# Teensy_ETH.net
KiCad netlist of a schematic drawn in EAGLE
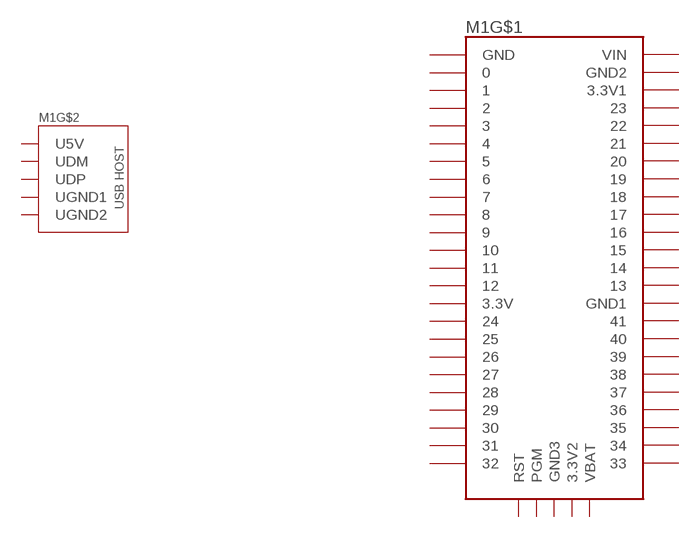
[diagram p0: schematic, sheet 1]
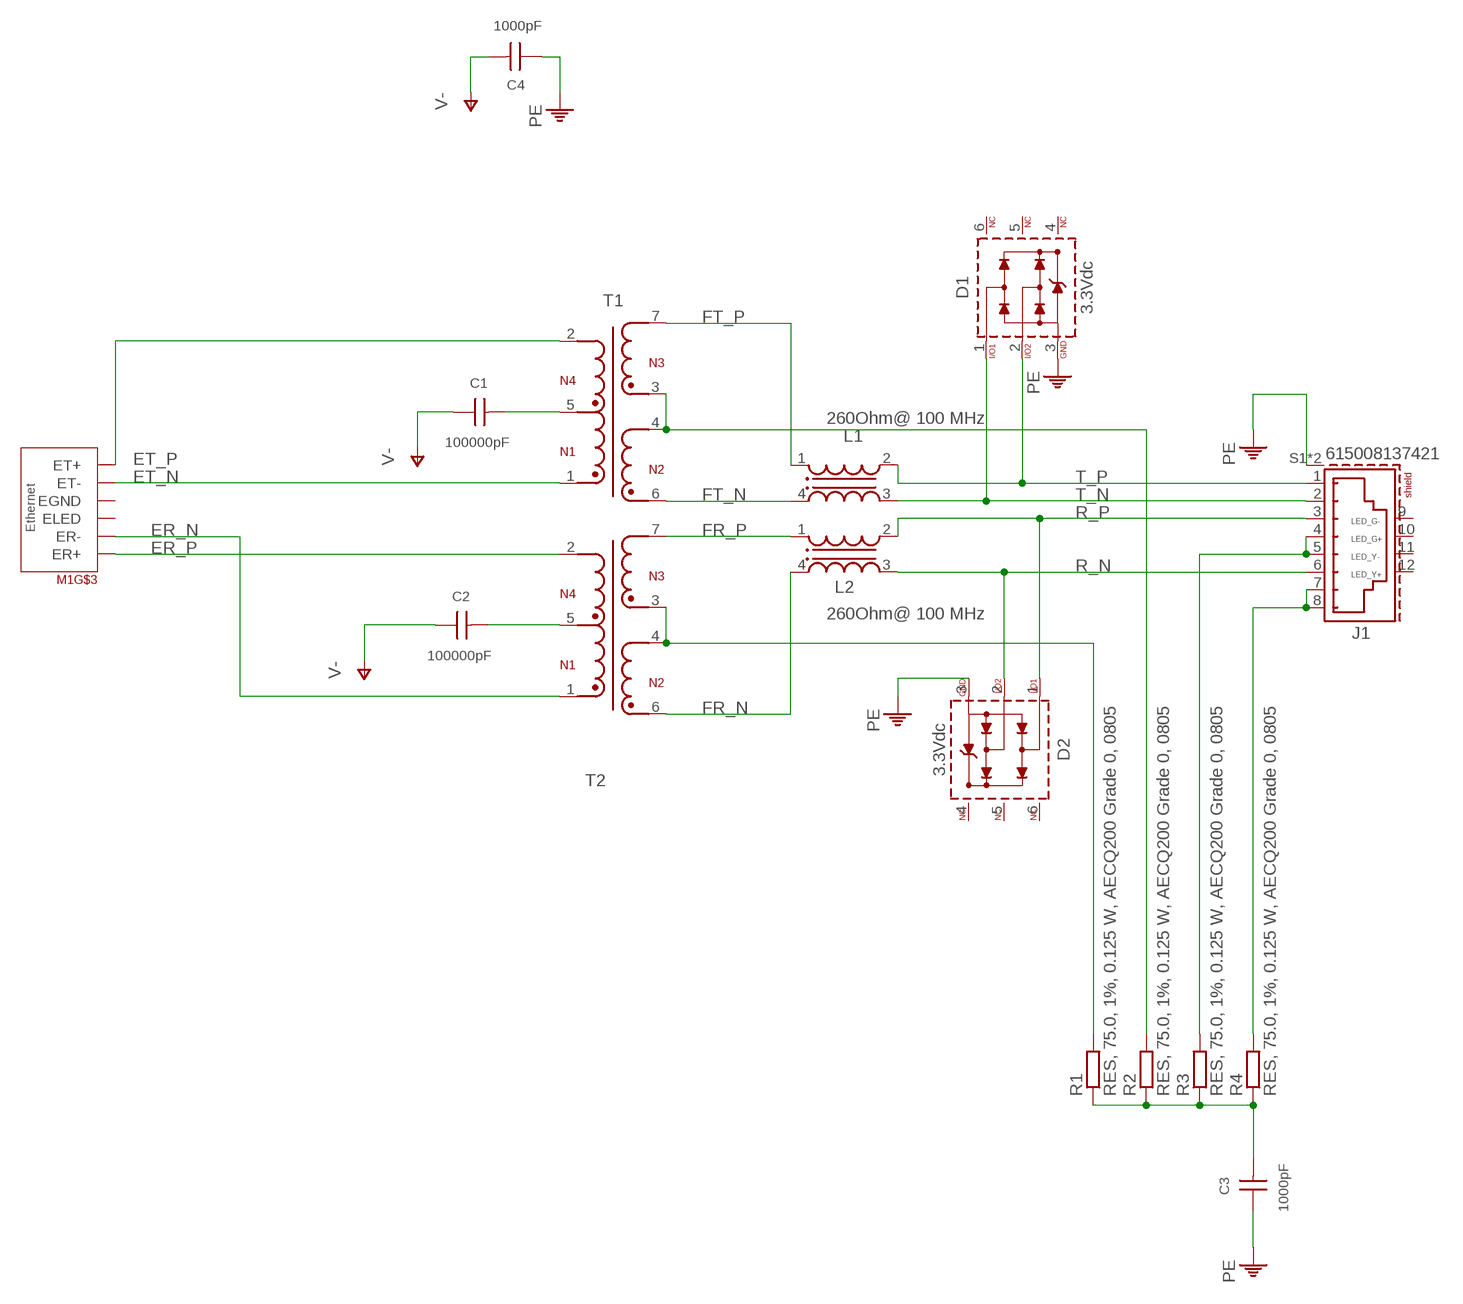
[diagram p1: schematic, sheet 2]

(export (version "E")
  (design (tool "Eeschema 10.0.6"))
  (components
    (comp (ref "C1")
      (value "100000pF")
      (footprint "eagle-import:WCAP-CSST_0603_R")
      (libsource (lib "eagle-import") (part "WCAP-CSST_0603_R_885382206004"))
    )
    (comp (ref "C2")
      (value "100000pF")
      (footprint "eagle-import:WCAP-CSST_0603_R")
      (libsource (lib "eagle-import") (part "WCAP-CSST_0603_R_885382206004"))
    )
    (comp (ref "C3")
      (value "1000pF")
      (footprint "eagle-import:WCAP-CSMH_1206_H1.6_R")
      (libsource (lib "eagle-import") (part "WCAP-CSMH_1206_H1.6_885342208024"))
    )
    (comp (ref "C4")
      (value "1000pF")
      (footprint "eagle-import:WCAP-CSMH_1206_H1.6_R")
      (libsource (lib "eagle-import") (part "WCAP-CSMH_1206_H1.6_885342208024"))
    )
    (comp (ref "D1")
      (value "3.3Vdc")
      (footprint "eagle-import:WE-TVS_DFN1210-6L")
      (libsource (lib "eagle-import") (part "WE-TVS-SS_DFN1210-6L_824012823"))
    )
    (comp (ref "D2")
      (value "3.3Vdc")
      (footprint "eagle-import:WE-TVS_DFN1210-6L")
      (libsource (lib "eagle-import") (part "WE-TVS-SS_DFN1210-6L_824012823"))
    )
    (comp (ref "J1")
      (value "615008137421")
      (footprint "eagle-import:615008137421")
      (libsource (lib "eagle-import") (part "615008137421"))
    )
    (comp (ref "L1")
      (value "260Ohm@ 100 MHz")
      (footprint "eagle-import:WE-CNSW_0805")
      (libsource (lib "eagle-import") (part "WE-CNSW_0805_744231261"))
    )
    (comp (ref "L2")
      (value "260Ohm@ 100 MHz")
      (footprint "eagle-import:WE-CNSW_0805")
      (libsource (lib "eagle-import") (part "WE-CNSW_0805_744231261"))
    )
    (comp (ref "M1")
      (value "TEENSY4.1")
      (footprint "eagle-import:TEENSY4.1")
      (libsource (lib "eagle-import") (part "TEENSY4.1"))
    )
    (comp (ref "R1")
      (value "RES, 75.0, 1%, 0.125 W, AECQ200 Grade 0, 0805")
      (footprint "eagle-import:R0805")
      (libsource (lib "eagle-import") (part "R-EU_R0805"))
    )
    (comp (ref "R2")
      (value "RES, 75.0, 1%, 0.125 W, AECQ200 Grade 0, 0805")
      (footprint "eagle-import:R0805")
      (libsource (lib "eagle-import") (part "R-EU_R0805"))
    )
    (comp (ref "R3")
      (value "RES, 75.0, 1%, 0.125 W, AECQ200 Grade 0, 0805")
      (footprint "eagle-import:R0805")
      (libsource (lib "eagle-import") (part "R-EU_R0805"))
    )
    (comp (ref "R4")
      (value "RES, 75.0, 1%, 0.125 W, AECQ200 Grade 0, 0805")
      (footprint "eagle-import:R0805")
      (libsource (lib "eagle-import") (part "R-EU_R0805"))
    )
    (comp (ref "T1")
      (value "WE-STST_4532_74930000")
      (footprint "eagle-import:WE-STST_74930000")
      (libsource (lib "eagle-import") (part "WE-STST_4532_74930000"))
    )
    (comp (ref "T2")
      (value "WE-STST_4532_74930000")
      (footprint "eagle-import:WE-STST_74930000")
      (libsource (lib "eagle-import") (part "WE-STST_4532_74930000"))
    )
  )
  (nets
    (net (code "1") (name "ER_N") (class "Default")
      (node (ref "M1") (pin "ER-") (pinfunction "ER-_ER-") (pintype "bidirectional"))
      (node (ref "T2") (pin "1") (pinfunction "1_1") (pintype "passive"))
    )
    (net (code "2") (name "ER_P") (class "Default")
      (node (ref "M1") (pin "ER+") (pinfunction "ER+_ER+") (pintype "bidirectional"))
      (node (ref "T2") (pin "2") (pinfunction "2_2") (pintype "passive"))
    )
    (net (code "3") (name "ET_N") (class "Default")
      (node (ref "M1") (pin "ET+") (pinfunction "ET-_ET+") (pintype "bidirectional"))
      (node (ref "T1") (pin "1") (pinfunction "1_1") (pintype "passive"))
    )
    (net (code "4") (name "ET_P") (class "Default")
      (node (ref "M1") (pin "ET-") (pinfunction "ET+_ET-") (pintype "bidirectional"))
      (node (ref "T1") (pin "2") (pinfunction "2_2") (pintype "passive"))
    )
    (net (code "5") (name "FR_N") (class "Default")
      (node (ref "L2") (pin "4") (pinfunction "1_4") (pintype "passive"))
      (node (ref "T2") (pin "6") (pinfunction "6_6") (pintype "passive"))
    )
    (net (code "6") (name "FR_P") (class "Default")
      (node (ref "L2") (pin "1") (pinfunction "4_1") (pintype "passive"))
      (node (ref "T2") (pin "7") (pinfunction "7_7") (pintype "passive"))
    )
    (net (code "7") (name "FT_N") (class "Default")
      (node (ref "L1") (pin "4") (pinfunction "1_4") (pintype "passive"))
      (node (ref "T1") (pin "6") (pinfunction "6_6") (pintype "passive"))
    )
    (net (code "8") (name "FT_P") (class "Default")
      (node (ref "L1") (pin "1") (pinfunction "4_1") (pintype "passive"))
      (node (ref "T1") (pin "7") (pinfunction "7_7") (pintype "passive"))
    )
    (net (code "9") (name "Net-(C1-Pad2)") (class "Default")
      (node (ref "C1") (pin "2") (pinfunction "2_2") (pintype "passive"))
      (node (ref "T1") (pin "5") (pinfunction "5_5") (pintype "passive"))
    )
    (net (code "10") (name "Net-(C2-Pad2)") (class "Default")
      (node (ref "C2") (pin "2") (pinfunction "2_2") (pintype "passive"))
      (node (ref "T2") (pin "5") (pinfunction "5_5") (pintype "passive"))
    )
    (net (code "11") (name "Net-(C3-Pad2)") (class "Default")
      (node (ref "C3") (pin "2") (pinfunction "2_2") (pintype "passive"))
      (node (ref "R1") (pin "1") (pinfunction "1_1") (pintype "passive"))
      (node (ref "R2") (pin "1") (pinfunction "1_1") (pintype "passive"))
      (node (ref "R3") (pin "1") (pinfunction "1_1") (pintype "passive"))
      (node (ref "R4") (pin "1") (pinfunction "1_1") (pintype "passive"))
    )
    (net (code "12") (name "Net-(J1-Pad4)") (class "Default")
      (node (ref "J1") (pin "4") (pinfunction "4_4") (pintype "passive"))
      (node (ref "J1") (pin "5") (pinfunction "5_5") (pintype "passive"))
      (node (ref "R3") (pin "2") (pinfunction "2_2") (pintype "passive"))
    )
    (net (code "13") (name "Net-(J1-Pad7)") (class "Default")
      (node (ref "J1") (pin "7") (pinfunction "7_7") (pintype "passive"))
      (node (ref "J1") (pin "8") (pinfunction "8_8") (pintype "passive"))
      (node (ref "R4") (pin "2") (pinfunction "2_2") (pintype "passive"))
    )
    (net (code "14") (name "Net-(R1-Pad2)") (class "Default")
      (node (ref "R1") (pin "2") (pinfunction "2_2") (pintype "passive"))
      (node (ref "T2") (pin "3") (pinfunction "3_3") (pintype "passive"))
      (node (ref "T2") (pin "4") (pinfunction "4_4") (pintype "passive"))
    )
    (net (code "15") (name "Net-(R2-Pad2)") (class "Default")
      (node (ref "R2") (pin "2") (pinfunction "2_2") (pintype "passive"))
      (node (ref "T1") (pin "3") (pinfunction "3_3") (pintype "passive"))
      (node (ref "T1") (pin "4") (pinfunction "4_4") (pintype "passive"))
    )
    (net (code "16") (name "PE") (class "Default")
      (node (ref "C3") (pin "1") (pinfunction "1_1") (pintype "passive"))
      (node (ref "C4") (pin "1") (pinfunction "1_1") (pintype "passive"))
      (node (ref "D1") (pin "3") (pinfunction "GND_3") (pintype "passive"))
      (node (ref "D2") (pin "3") (pinfunction "GND_3") (pintype "passive"))
      (node (ref "J1") (pin "S1") (pinfunction "SHIELD_S1") (pintype "passive"))
      (node (ref "J1") (pin "S2") (pinfunction "SHIELD_S2") (pintype "passive"))
    )
    (net (code "17") (name "R_N") (class "Default")
      (node (ref "D2") (pin "2") (pinfunction "I/O2_2") (pintype "passive"))
      (node (ref "J1") (pin "6") (pinfunction "6_6") (pintype "passive"))
      (node (ref "L2") (pin "3") (pinfunction "2_3") (pintype "passive"))
    )
    (net (code "18") (name "R_P") (class "Default")
      (node (ref "D2") (pin "1") (pinfunction "I/O1_1") (pintype "passive"))
      (node (ref "J1") (pin "3") (pinfunction "3_3") (pintype "passive"))
      (node (ref "L2") (pin "2") (pinfunction "3_2") (pintype "passive"))
    )
    (net (code "19") (name "T_N") (class "Default")
      (node (ref "D1") (pin "1") (pinfunction "I/O1_1") (pintype "passive"))
      (node (ref "J1") (pin "2") (pinfunction "2_2") (pintype "passive"))
      (node (ref "L1") (pin "3") (pinfunction "2_3") (pintype "passive"))
    )
    (net (code "20") (name "T_P") (class "Default")
      (node (ref "D1") (pin "2") (pinfunction "I/O2_2") (pintype "passive"))
      (node (ref "J1") (pin "1") (pinfunction "1_1") (pintype "passive"))
      (node (ref "L1") (pin "2") (pinfunction "3_2") (pintype "passive"))
    )
    (net (code "21") (name "V-") (class "Default")
      (node (ref "C1") (pin "1") (pinfunction "1_1") (pintype "passive"))
      (node (ref "C2") (pin "1") (pinfunction "1_1") (pintype "passive"))
      (node (ref "C4") (pin "2") (pinfunction "2_2") (pintype "passive"))
    )
    (net (code "22") (name "unconnected-(D1-NC-Pad4)") (class "Default")
      (node (ref "D1") (pin "4") (pinfunction "NC_4") (pintype "passive"))
    )
    (net (code "23") (name "unconnected-(D1-NC1-Pad5)") (class "Default")
      (node (ref "D1") (pin "5") (pinfunction "NC1_5") (pintype "passive"))
    )
    (net (code "24") (name "unconnected-(D1-NC2-Pad6)") (class "Default")
      (node (ref "D1") (pin "6") (pinfunction "NC2_6") (pintype "passive"))
    )
    (net (code "25") (name "unconnected-(D2-NC-Pad4)") (class "Default")
      (node (ref "D2") (pin "4") (pinfunction "NC_4") (pintype "passive"))
    )
    (net (code "26") (name "unconnected-(D2-NC1-Pad5)") (class "Default")
      (node (ref "D2") (pin "5") (pinfunction "NC1_5") (pintype "passive"))
    )
    (net (code "27") (name "unconnected-(D2-NC2-Pad6)") (class "Default")
      (node (ref "D2") (pin "6") (pinfunction "NC2_6") (pintype "passive"))
    )
    (net (code "28") (name "unconnected-(J1-G+-Pad10)") (class "Default")
      (node (ref "J1") (pin "10") (pinfunction "G+_10") (pintype "passive"))
    )
    (net (code "29") (name "unconnected-(J1-G--Pad9)") (class "Default")
      (node (ref "J1") (pin "9") (pinfunction "G-_9") (pintype "passive"))
    )
    (net (code "30") (name "unconnected-(J1-Y+-Pad12)") (class "Default")
      (node (ref "J1") (pin "12") (pinfunction "Y+_12") (pintype "passive"))
    )
    (net (code "31") (name "unconnected-(J1-Y--Pad11)") (class "Default")
      (node (ref "J1") (pin "11") (pinfunction "Y-_11") (pintype "passive"))
    )
    (net (code "32") (name "unconnected-(M1-Pad2)") (class "Default")
      (node (ref "M1") (pin "2") (pinfunction "2_2") (pintype "bidirectional"))
    )
    (net (code "33") (name "unconnected-(M1-Pad3)") (class "Default")
      (node (ref "M1") (pin "3") (pinfunction "3_3") (pintype "bidirectional"))
    )
    (net (code "34") (name "unconnected-(M1-Pad4)") (class "Default")
      (node (ref "M1") (pin "4") (pinfunction "4_4") (pintype "bidirectional"))
    )
    (net (code "35") (name "unconnected-(M1-Pad5)") (class "Default")
      (node (ref "M1") (pin "5") (pinfunction "5_5") (pintype "bidirectional"))
    )
    (net (code "36") (name "unconnected-(M1-Pad6)") (class "Default")
      (node (ref "M1") (pin "6") (pinfunction "6_6") (pintype "bidirectional"))
    )
    (net (code "37") (name "unconnected-(M1-Pad7)") (class "Default")
      (node (ref "M1") (pin "7") (pinfunction "7_7") (pintype "bidirectional"))
    )
    (net (code "38") (name "unconnected-(M1-Pad8)") (class "Default")
      (node (ref "M1") (pin "8") (pinfunction "8_8") (pintype "bidirectional"))
    )
    (net (code "39") (name "unconnected-(M1-Pad9)") (class "Default")
      (node (ref "M1") (pin "9") (pinfunction "9_9") (pintype "bidirectional"))
    )
    (net (code "40") (name "unconnected-(M1-Pad24)") (class "Default")
      (node (ref "M1") (pin "24") (pinfunction "24_24") (pintype "bidirectional"))
    )
    (net (code "41") (name "unconnected-(M1-Pad25)") (class "Default")
      (node (ref "M1") (pin "25") (pinfunction "25_25") (pintype "bidirectional"))
    )
    (net (code "42") (name "unconnected-(M1-Pad26)") (class "Default")
      (node (ref "M1") (pin "26") (pinfunction "26_26") (pintype "bidirectional"))
    )
    (net (code "43") (name "unconnected-(M1-Pad27)") (class "Default")
      (node (ref "M1") (pin "27") (pinfunction "27_27") (pintype "bidirectional"))
    )
    (net (code "44") (name "unconnected-(M1-Pad28)") (class "Default")
      (node (ref "M1") (pin "28") (pinfunction "28_28") (pintype "bidirectional"))
    )
    (net (code "45") (name "unconnected-(M1-Pad29)") (class "Default")
      (node (ref "M1") (pin "29") (pinfunction "29_29") (pintype "bidirectional"))
    )
    (net (code "46") (name "unconnected-(M1-Pad30)") (class "Default")
      (node (ref "M1") (pin "30") (pinfunction "30_30") (pintype "bidirectional"))
    )
    (net (code "47") (name "unconnected-(M1-Pad32)") (class "Default")
      (node (ref "M1") (pin "32") (pinfunction "32_32") (pintype "bidirectional"))
    )
    (net (code "48") (name "unconnected-(M1-Pad33)") (class "Default")
      (node (ref "M1") (pin "33") (pinfunction "33_33") (pintype "bidirectional"))
    )
    (net (code "49") (name "unconnected-(M1-Pad34)") (class "Default")
      (node (ref "M1") (pin "34") (pinfunction "34_34") (pintype "bidirectional"))
    )
    (net (code "50") (name "unconnected-(M1-Pad35)") (class "Default")
      (node (ref "M1") (pin "35") (pinfunction "35_35") (pintype "bidirectional"))
    )
    (net (code "51") (name "unconnected-(M1-Pad36)") (class "Default")
      (node (ref "M1") (pin "36") (pinfunction "36_36") (pintype "bidirectional"))
    )
    (net (code "52") (name "unconnected-(M1-Pad37)") (class "Default")
      (node (ref "M1") (pin "37") (pinfunction "37_37") (pintype "bidirectional"))
    )
    (net (code "53") (name "unconnected-(M1-Pad38)") (class "Default")
      (node (ref "M1") (pin "38") (pinfunction "38_38") (pintype "bidirectional"))
    )
    (net (code "54") (name "unconnected-(M1-Pad39)") (class "Default")
      (node (ref "M1") (pin "39") (pinfunction "39_39") (pintype "bidirectional"))
    )
    (net (code "55") (name "unconnected-(M1-Pad40)") (class "Default")
      (node (ref "M1") (pin "40") (pinfunction "40_40") (pintype "bidirectional"))
    )
    (net (code "56") (name "unconnected-(M1-Pad41)") (class "Default")
      (node (ref "M1") (pin "41") (pinfunction "41_41") (pintype "bidirectional"))
    )
    (net (code "57") (name "unconnected-(M1-PadELED)") (class "Default")
      (node (ref "M1") (pin "ELED") (pinfunction "ELED_ELED") (pintype "bidirectional"))
    )
    (net (code "58") (name "unconnected-(M1-PadGND)") (class "Default")
      (node (ref "M1") (pin "GND") (pinfunction "GND_GND") (pintype "bidirectional"))
    )
    (net (code "59") (name "unconnected-(M1-PadGND1)") (class "Default")
      (node (ref "M1") (pin "GND1") (pinfunction "GND1_GND1") (pintype "bidirectional"))
    )
    (net (code "60") (name "unconnected-(M1-PadRST)") (class "Default")
      (node (ref "M1") (pin "RST") (pinfunction "RST_RST") (pintype "bidirectional"))
    )
    (net (code "61") (name "unconnected-(M1-PadVBAT)") (class "Default")
      (node (ref "M1") (pin "VBAT") (pinfunction "VBAT_VBAT") (pintype "bidirectional"))
    )
    (net (code "62") (name "unconnected-(M1-PadVIN)") (class "Default")
      (node (ref "M1") (pin "VIN") (pinfunction "VIN_VIN") (pintype "bidirectional"))
    )
    (net (code "63") (name "unconnected-(M1A-0-Pad0{slash}RX)") (class "Default")
      (node (ref "M1") (pin "0/RX") (pinfunction "0_0/RX") (pintype "bidirectional"))
    )
    (net (code "64") (name "unconnected-(M1A-1-Pad1{slash}TX)") (class "Default")
      (node (ref "M1") (pin "1/TX") (pinfunction "1_1/TX") (pintype "bidirectional"))
    )
    (net (code "65") (name "unconnected-(M1A-3.3V-Pad3V3)") (class "Default")
      (node (ref "M1") (pin "3V3") (pinfunction "3.3V_3V3") (pintype "bidirectional"))
    )
    (net (code "66") (name "unconnected-(M1A-3.3V1-Pad3V3_LO)") (class "Default")
      (node (ref "M1") (pin "3V3_LO") (pinfunction "3.3V1_3V3_LO") (pintype "bidirectional"))
    )
    (net (code "67") (name "unconnected-(M1A-3.3V2-PadV33)") (class "Default")
      (node (ref "M1") (pin "V33") (pinfunction "3.3V2_V33") (pintype "bidirectional"))
    )
    (net (code "68") (name "unconnected-(M1A-10-Pad10{slash}CS)") (class "Default")
      (node (ref "M1") (pin "10/CS") (pinfunction "10_10/CS") (pintype "bidirectional"))
    )
    (net (code "69") (name "unconnected-(M1A-11-Pad11{slash}MOSI)") (class "Default")
      (node (ref "M1") (pin "11/MOSI") (pinfunction "11_11/MOSI") (pintype "bidirectional"))
    )
    (net (code "70") (name "unconnected-(M1A-12-Pad12{slash}MISO)") (class "Default")
      (node (ref "M1") (pin "12/MISO") (pinfunction "12_12/MISO") (pintype "bidirectional"))
    )
    (net (code "71") (name "unconnected-(M1A-13-Pad13{slash}SCK)") (class "Default")
      (node (ref "M1") (pin "13/SCK") (pinfunction "13_13/SCK") (pintype "bidirectional"))
    )
    (net (code "72") (name "unconnected-(M1A-14-Pad14{slash}A0)") (class "Default")
      (node (ref "M1") (pin "14/A0") (pinfunction "14_14/A0") (pintype "bidirectional"))
    )
    (net (code "73") (name "unconnected-(M1A-15-Pad15{slash}A1)") (class "Default")
      (node (ref "M1") (pin "15/A1") (pinfunction "15_15/A1") (pintype "bidirectional"))
    )
    (net (code "74") (name "unconnected-(M1A-16-Pad16{slash}A2)") (class "Default")
      (node (ref "M1") (pin "16/A2") (pinfunction "16_16/A2") (pintype "bidirectional"))
    )
    (net (code "75") (name "unconnected-(M1A-17-Pad17{slash}A3)") (class "Default")
      (node (ref "M1") (pin "17/A3") (pinfunction "17_17/A3") (pintype "bidirectional"))
    )
    (net (code "76") (name "unconnected-(M1A-18-Pad18{slash}A4{slash}SDA)") (class "Default")
      (node (ref "M1") (pin "18/A4/SDA") (pinfunction "18_18/A4/SDA") (pintype "bidirectional"))
    )
    (net (code "77") (name "unconnected-(M1A-19-Pad19{slash}A5{slash}SCL)") (class "Default")
      (node (ref "M1") (pin "19/A5/SCL") (pinfunction "19_19/A5/SCL") (pintype "bidirectional"))
    )
    (net (code "78") (name "unconnected-(M1A-20-Pad20{slash}A6)") (class "Default")
      (node (ref "M1") (pin "20/A6") (pinfunction "20_20/A6") (pintype "bidirectional"))
    )
    (net (code "79") (name "unconnected-(M1A-21-Pad21{slash}A7)") (class "Default")
      (node (ref "M1") (pin "21/A7") (pinfunction "21_21/A7") (pintype "bidirectional"))
    )
    (net (code "80") (name "unconnected-(M1A-22-Pad22{slash}A8)") (class "Default")
      (node (ref "M1") (pin "22/A8") (pinfunction "22_22/A8") (pintype "bidirectional"))
    )
    (net (code "81") (name "unconnected-(M1A-23-Pad23{slash}A9)") (class "Default")
      (node (ref "M1") (pin "23/A9") (pinfunction "23_23/A9") (pintype "bidirectional"))
    )
    (net (code "82") (name "unconnected-(M1A-31-Pad31{slash}A12)") (class "Default")
      (node (ref "M1") (pin "31/A12") (pinfunction "31_31/A12") (pintype "bidirectional"))
    )
    (net (code "83") (name "unconnected-(M1A-GND2-PadAGND)") (class "Default")
      (node (ref "M1") (pin "AGND") (pinfunction "GND2_AGND") (pintype "bidirectional"))
    )
    (net (code "84") (name "unconnected-(M1A-GND3-PadGND2)") (class "Default")
      (node (ref "M1") (pin "GND2") (pinfunction "GND3_GND2") (pintype "bidirectional"))
    )
    (net (code "85") (name "unconnected-(M1A-PGM-PadPROG)") (class "Default")
      (node (ref "M1") (pin "PROG") (pinfunction "PGM_PROG") (pintype "bidirectional"))
    )
    (net (code "86") (name "unconnected-(M1B-U5V-PadUVHST)") (class "Default")
      (node (ref "M1") (pin "UVHST") (pinfunction "U5V_UVHST") (pintype "bidirectional"))
    )
    (net (code "87") (name "unconnected-(M1B-UDM-PadUD-)") (class "Default")
      (node (ref "M1") (pin "UD-") (pinfunction "UDM_UD-") (pintype "bidirectional"))
    )
    (net (code "88") (name "unconnected-(M1B-UDP-PadUD+)") (class "Default")
      (node (ref "M1") (pin "UD+") (pinfunction "UDP_UD+") (pintype "bidirectional"))
    )
    (net (code "89") (name "unconnected-(M1B-UGND1-PadGND-U1)") (class "Default")
      (node (ref "M1") (pin "GND-U1") (pinfunction "UGND1_GND-U1") (pintype "bidirectional"))
    )
    (net (code "90") (name "unconnected-(M1B-UGND2-PadGND-U2)") (class "Default")
      (node (ref "M1") (pin "GND-U2") (pinfunction "UGND2_GND-U2") (pintype "bidirectional"))
    )
    (net (code "91") (name "unconnected-(M1C-EGND-PadGND-E)") (class "Default")
      (node (ref "M1") (pin "GND-E") (pinfunction "EGND_GND-E") (pintype "bidirectional"))
    )
  )
)
